# DLP.net
KiCad netlist of a schematic drawn in Altium Designer
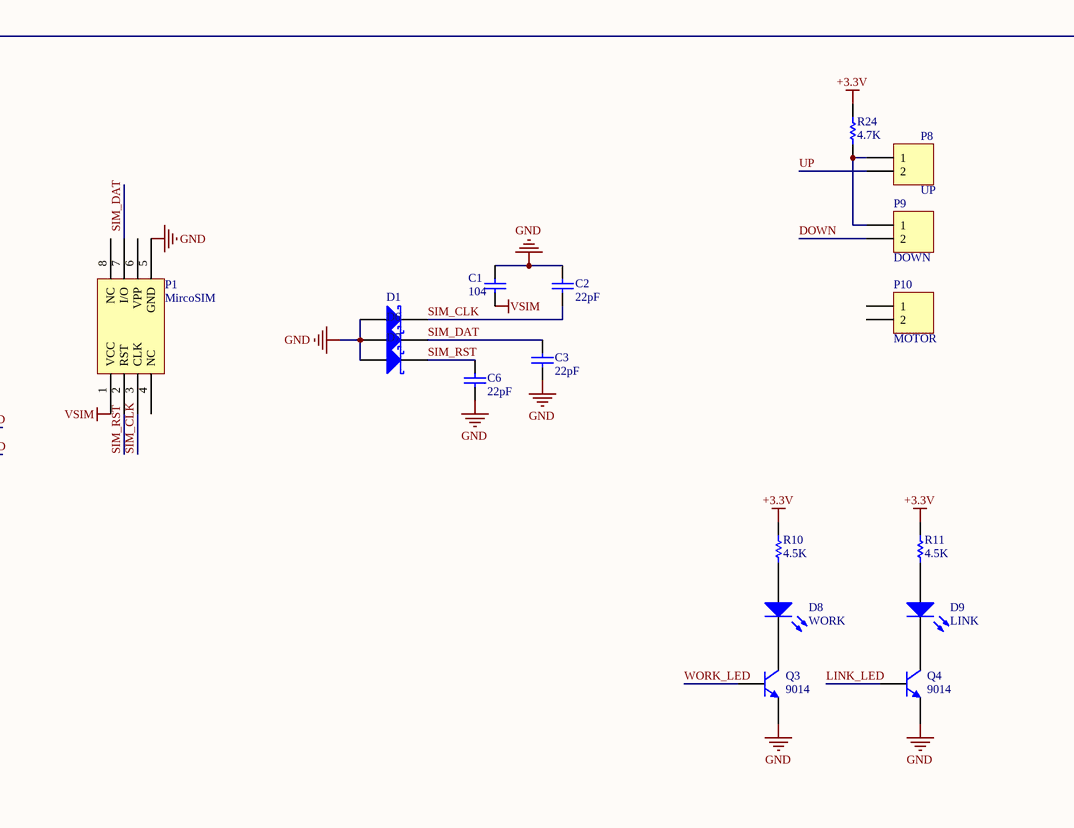
[diagram p0: DLP.SchDoc, top right]
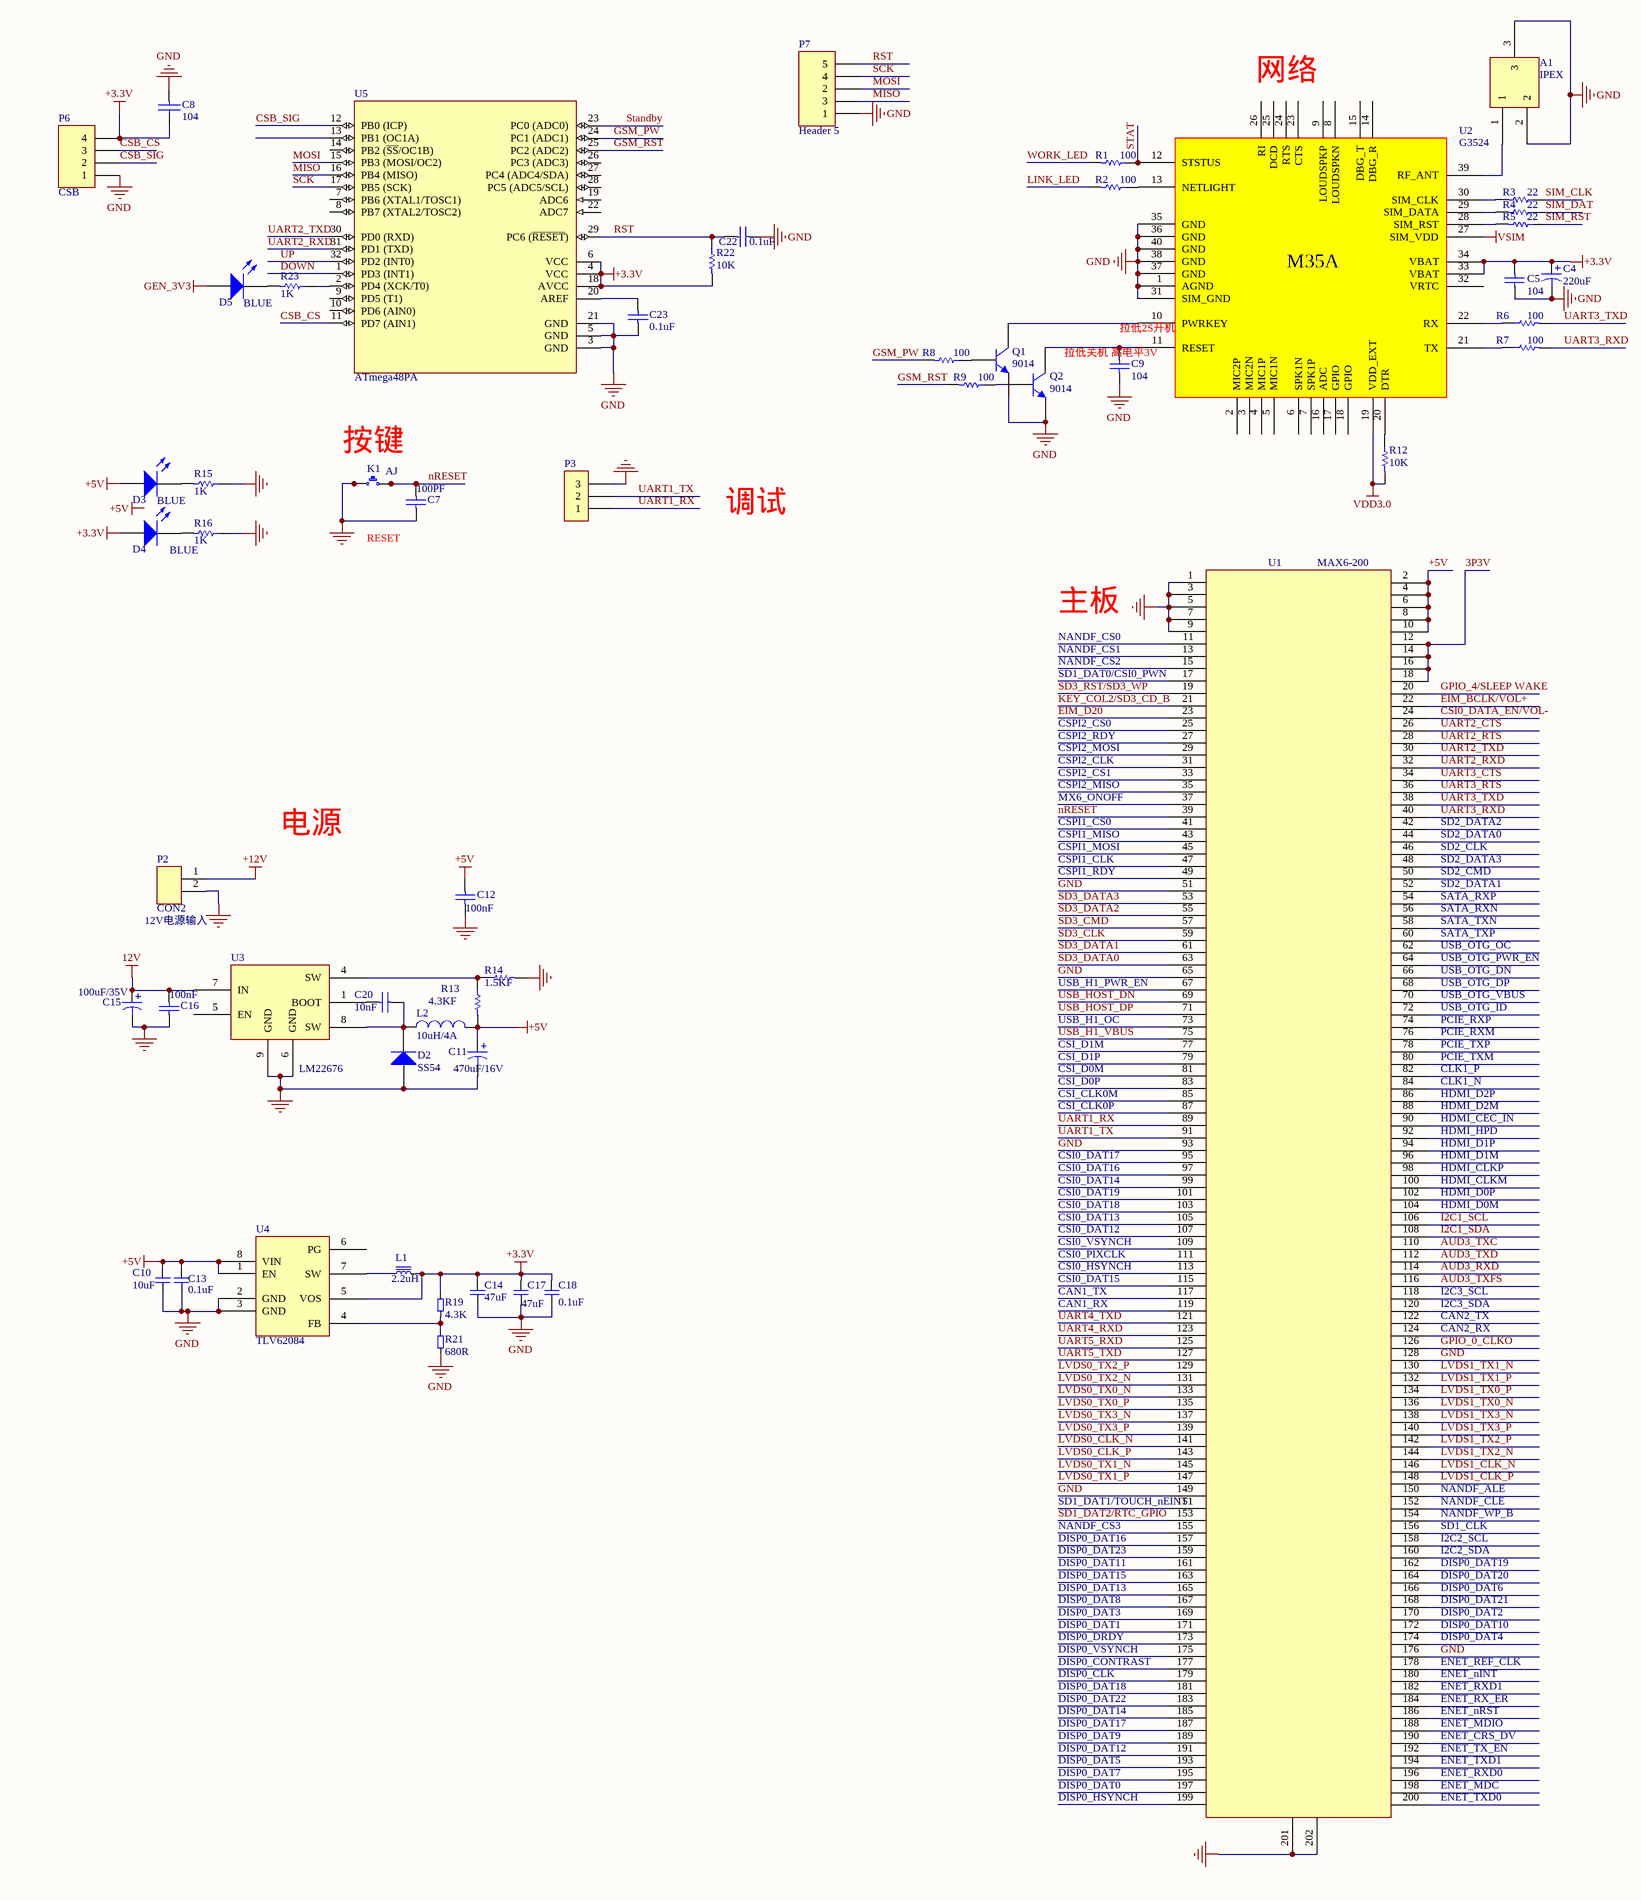
[diagram p1: DLP.SchDoc, bottom left]
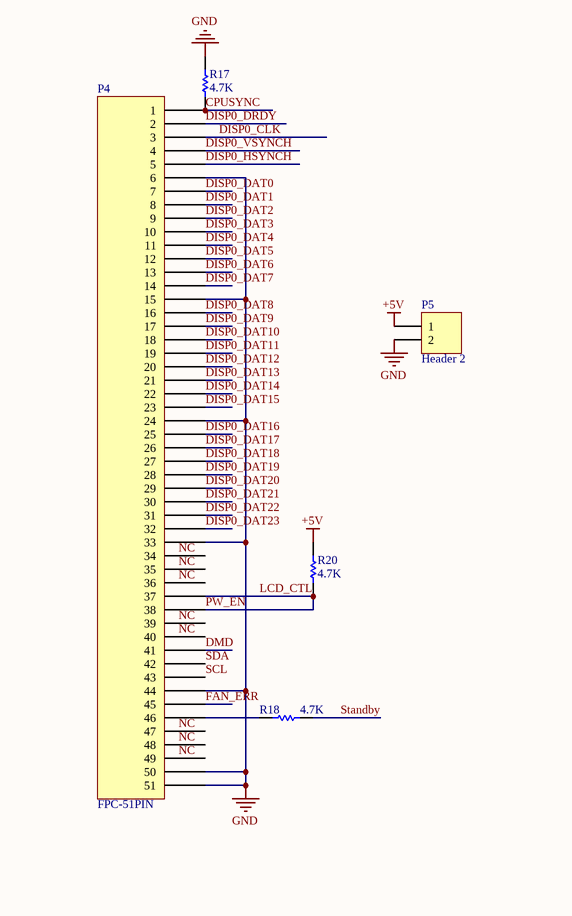
[diagram p2: DLP.SchDoc, bottom right]

(export (version "E")
  (design (tool "Eeschema 10.0.6"))
  (components
    (comp (ref "A1") (value "IPEX") (footprint "IPEX") (libsource (lib "TANK") (part "IPEX")))
    (comp (ref "C1")
      (value "104")
      (footprint "0603")
      (description "Capacitor")
      (fields (field (name "Comment") "Cap") (field (name "PUBLISHER") "Altium Limited"))
      (libsource (lib "Miscellaneous Devices") (part "Cap"))
    )
    (comp (ref "C2")
      (value "22pF")
      (footprint "0603")
      (description "Capacitor")
      (fields (field (name "Comment") "Cap") (field (name "PUBLISHER") "Altium Limited"))
      (libsource (lib "Miscellaneous Devices") (part "Cap"))
    )
    (comp (ref "C3")
      (value "22pF")
      (footprint "0603")
      (description "Capacitor")
      (fields (field (name "Comment") "Cap") (field (name "PUBLISHER") "Altium Limited"))
      (libsource (lib "Miscellaneous Devices") (part "Cap"))
    )
    (comp (ref "C4")
      (value "220uF")
      (footprint "C7343")
      (description "Polarized Capacitor (Surface Mount)")
      (fields (field (name "Comment") "Cap Pol3") (field (name "PUBLISHER") "Altium Limited"))
      (libsource (lib "Miscellaneous Devices") (part "Cap Pol3"))
    )
    (comp (ref "C5")
      (value "104")
      (footprint "0603")
      (description "Capacitor")
      (fields (field (name "Comment") "Cap") (field (name "PUBLISHER") "Altium Limited"))
      (libsource (lib "Miscellaneous Devices") (part "Cap"))
    )
    (comp (ref "C6")
      (value "22pF")
      (footprint "0603")
      (description "Capacitor")
      (fields (field (name "Comment") "Cap") (field (name "PUBLISHER") "Altium Limited"))
      (libsource (lib "Miscellaneous Devices") (part "Cap"))
    )
    (comp (ref "C7")
      (value "100PF")
      (footprint "0603")
      (description "Capacitor")
      (libsource (lib "*") (part "Cap"))
    )
    (comp (ref "C8") (value "104") (footprint "0603") (libsource (lib "*") (part "CAP")))
    (comp (ref "C9")
      (value "104")
      (footprint "0603")
      (description "Capacitor")
      (fields (field (name "Comment") "Cap") (field (name "PUBLISHER") "Altium Limited"))
      (libsource (lib "Miscellaneous Devices") (part "Cap"))
    )
    (comp (ref "C10")
      (value "10uF")
      (footprint "0603")
      (description "电容")
      (libsource (lib "LDT-SCH") (part "电容"))
    )
    (comp (ref "C11")
      (value "470uF/16V")
      (footprint "C7343")
      (description "Polarized Capacitor (Radial)")
      (libsource (lib "*") (part "Cap Pol1"))
    )
    (comp (ref "C12")
      (value "100nF")
      (footprint "0603")
      (description "Capacitor")
      (libsource (lib "*") (part "Cap"))
    )
    (comp (ref "C13")
      (value "0.1uF")
      (footprint "0603")
      (description "电容")
      (libsource (lib "LDT-SCH") (part "电容"))
    )
    (comp (ref "C14")
      (value "47uF")
      (footprint "C1206")
      (description "电容")
      (libsource (lib "LDT-SCH") (part "电容"))
    )
    (comp (ref "C15")
      (value "100uF/35V")
      (footprint "C7343")
      (description "Polarized Capacitor (Radial)")
      (libsource (lib "*") (part "Cap Pol1"))
    )
    (comp (ref "C16")
      (value "100nF")
      (footprint "0603")
      (description "Capacitor")
      (libsource (lib "*") (part "Cap"))
    )
    (comp (ref "C17")
      (value "47uF")
      (footprint "C1206")
      (description "电容")
      (libsource (lib "LDT-SCH") (part "电容"))
    )
    (comp (ref "C18")
      (value "0.1uF")
      (footprint "0603")
      (description "电容")
      (libsource (lib "LDT-SCH") (part "电容"))
    )
    (comp (ref "C20")
      (value "10nF")
      (footprint "0603")
      (description "Capacitor")
      (libsource (lib "*") (part "Cap"))
    )
    (comp (ref "C22")
      (value "0.1uF")
      (footprint "0603")
      (description "Capacitor")
      (fields (field (name "Comment") "Cap") (field (name "PUBLISHER") "Altium Limited"))
      (libsource (lib "Miscellaneous Devices") (part "Cap"))
    )
    (comp (ref "C23")
      (value "0.1uF")
      (footprint "0603")
      (description "Capacitor")
      (fields (field (name "Comment") "Cap") (field (name "PUBLISHER") "Altium Limited"))
      (libsource (lib "Miscellaneous Devices") (part "Cap"))
    )
    (comp (ref "D1")
      (value "RL0603E012M100K")
      (footprint "0603")
      (description "Schottky Rectifier")
      (fields (field (name "PUBLISHER") "Altium Limited"))
      (libsource (lib "Miscellaneous Devices") (part "Diode 18TQ045"))
    )
    (comp (ref "D2")
      (value "SS54")
      (footprint "SMA")
      (description "3 Amp Medium Power Silicon Rectifier Diode")
      (libsource (lib "*") (part "Diode 1N5408"))
    )
    (comp (ref "D3")
      (value "BLUE")
      (footprint "0603-LED")
      (description "Typical RED, GREEN, YELLOW, AMBER GaAs LED")
      (libsource (lib "*") (part "LED2"))
    )
    (comp (ref "D4")
      (value "BLUE")
      (footprint "0603-LED")
      (description "Typical RED, GREEN, YELLOW, AMBER GaAs LED")
      (libsource (lib "*") (part "LED2"))
    )
    (comp (ref "D5")
      (value "BLUE")
      (footprint "0603-LED")
      (description "Typical RED, GREEN, YELLOW, AMBER GaAs LED")
      (libsource (lib "*") (part "LED2"))
    )
    (comp (ref "D6")
      (value "RL0603E012M100K")
      (footprint "0603")
      (description "Schottky Rectifier")
      (fields (field (name "PUBLISHER") "Altium Limited"))
      (libsource (lib "Miscellaneous Devices") (part "Diode 18TQ045"))
    )
    (comp (ref "D7")
      (value "RL0603E012M100K")
      (footprint "0603")
      (description "Schottky Rectifier")
      (fields (field (name "PUBLISHER") "Altium Limited"))
      (libsource (lib "Miscellaneous Devices") (part "Diode 18TQ045"))
    )
    (comp (ref "D8")
      (value "WORK")
      (footprint "0603-LED")
      (description "Typical RED, GREEN, YELLOW, AMBER GaAs LED")
      (fields (field (name "PUBLISHER") "Altium Limited"))
      (libsource (lib "Miscellaneous Devices") (part "LED2"))
    )
    (comp (ref "D9")
      (value "LINK")
      (footprint "0603-LED")
      (description "Typical RED, GREEN, YELLOW, AMBER GaAs LED")
      (fields (field (name "PUBLISHER") "Altium Limited"))
      (libsource (lib "Miscellaneous Devices") (part "LED2"))
    )
    (comp (ref "K1") (value "AJ") (footprint "4*4*1.5") (libsource (lib "*") (part "KEY_1")))
    (comp (ref "L1") (value "2.2uH") (footprint "L-6045") (libsource (lib "LDT-SCH") (part "功率电感")))
    (comp (ref "L2")
      (value "10uH/4A")
      (footprint "L-8040")
      (description "Inductor")
      (libsource (lib "*") (part "Inductor"))
    )
    (comp (ref "P1") (value "MircoSIM") (footprint "Micro SIM") (libsource (lib "TANK") (part "MircoSIM")))
    (comp (ref "P2") (value "CON2") (footprint "PH2.0-2P") (libsource (lib "*") (part "CON2")))
    (comp (ref "P3")
      (value "~")
      (footprint "HDR1X3")
      (description "Connector")
      (libsource (lib "*") (part "CON3"))
    )
    (comp (ref "P4")
      (value "FPC-51PIN")
      (footprint "FH26-51S-0.3SHW")
      (libsource (lib "TANK") (part "FPC-51PIN"))
    )
    (comp (ref "P5")
      (value "Header 2")
      (footprint "PH2.0-2P")
      (description "Header, 2-Pin")
      (fields (field (name "PUBLISHER") "Altium Limited"))
      (libsource (lib "Miscellaneous Connectors") (part "Header 2"))
    )
    (comp (ref "P6")
      (value "CSB")
      (footprint "HDR1X4")
      (description "Header, 4-Pin")
      (fields (field (name "PUBLISHER") "Altium Limited"))
      (libsource (lib "Miscellaneous Connectors") (part "Header 4"))
    )
    (comp (ref "P7")
      (value "Header 5")
      (footprint "HDR1X5")
      (description "Header, 5-Pin")
      (fields (field (name "PUBLISHER") "Altium Limited"))
      (libsource (lib "Miscellaneous Connectors") (part "Header 5"))
    )
    (comp (ref "P8")
      (value "UP")
      (footprint "1.25-2P")
      (description "Header, 2-Pin")
      (fields (field (name "PUBLISHER") "Altium Limited"))
      (libsource (lib "Miscellaneous Connectors") (part "Header 2"))
    )
    (comp (ref "P9")
      (value "DOWN")
      (footprint "1.25-2P")
      (description "Header, 2-Pin")
      (fields (field (name "PUBLISHER") "Altium Limited"))
      (libsource (lib "Miscellaneous Connectors") (part "Header 2"))
    )
    (comp (ref "P10")
      (value "MOTOR")
      (footprint "1.25-2P")
      (description "Header, 2-Pin")
      (fields (field (name "PUBLISHER") "Altium Limited"))
      (libsource (lib "Miscellaneous Connectors") (part "Header 2"))
    )
    (comp (ref "Q1")
      (value "9014")
      (footprint "SOT-23-NPN")
      (description "NPN General Purpose Amplifier")
      (fields (field (name "Comment") "NPN") (field (name "PUBLISHER") "Altium Limited"))
      (libsource (lib "FSC Discrete BJT") (part "2N5551"))
    )
    (comp (ref "Q2")
      (value "9014")
      (footprint "SOT-23-NPN")
      (description "NPN General Purpose Amplifier")
      (fields (field (name "Comment") "NPN") (field (name "PUBLISHER") "Altium Limited"))
      (libsource (lib "FSC Discrete BJT") (part "2N5551"))
    )
    (comp (ref "Q3")
      (value "9014")
      (footprint "SOT-23-NPN")
      (description "NPN General Purpose Amplifier")
      (fields (field (name "Comment") "NPN") (field (name "PUBLISHER") "Altium Limited"))
      (libsource (lib "FSC Discrete BJT") (part "2N5551"))
    )
    (comp (ref "Q4")
      (value "9014")
      (footprint "SOT-23-NPN")
      (description "NPN General Purpose Amplifier")
      (fields (field (name "Comment") "NPN") (field (name "PUBLISHER") "Altium Limited"))
      (libsource (lib "FSC Discrete BJT") (part "2N5551"))
    )
    (comp (ref "R1")
      (value "100")
      (footprint "0603")
      (description "Resistor")
      (fields (field (name "Comment") "Res1") (field (name "PUBLISHER") "Altium Limited"))
      (libsource (lib "Miscellaneous Devices") (part "Res1"))
    )
    (comp (ref "R2")
      (value "100")
      (footprint "0603")
      (description "Resistor")
      (fields (field (name "Comment") "Res1") (field (name "PUBLISHER") "Altium Limited"))
      (libsource (lib "Miscellaneous Devices") (part "Res1"))
    )
    (comp (ref "R3")
      (value "22")
      (footprint "0603")
      (description "Resistor")
      (fields (field (name "Comment") "Res1") (field (name "PUBLISHER") "Altium Limited"))
      (libsource (lib "Miscellaneous Devices") (part "Res1"))
    )
    (comp (ref "R4")
      (value "22")
      (footprint "0603")
      (description "Resistor")
      (fields (field (name "Comment") "Res1") (field (name "PUBLISHER") "Altium Limited"))
      (libsource (lib "Miscellaneous Devices") (part "Res1"))
    )
    (comp (ref "R5")
      (value "22")
      (footprint "0603")
      (description "Resistor")
      (fields (field (name "Comment") "Res1") (field (name "PUBLISHER") "Altium Limited"))
      (libsource (lib "Miscellaneous Devices") (part "Res1"))
    )
    (comp (ref "R6")
      (value "100")
      (footprint "0603")
      (description "Resistor")
      (fields (field (name "Comment") "Res1") (field (name "PUBLISHER") "Altium Limited"))
      (libsource (lib "Miscellaneous Devices") (part "Res1"))
    )
    (comp (ref "R7")
      (value "100")
      (footprint "0603")
      (description "Resistor")
      (fields (field (name "Comment") "Res1") (field (name "PUBLISHER") "Altium Limited"))
      (libsource (lib "Miscellaneous Devices") (part "Res1"))
    )
    (comp (ref "R8")
      (value "100")
      (footprint "0603")
      (description "Resistor")
      (fields (field (name "Comment") "Res1") (field (name "PUBLISHER") "Altium Limited"))
      (libsource (lib "Miscellaneous Devices") (part "Res1"))
    )
    (comp (ref "R9")
      (value "100")
      (footprint "0603")
      (description "Resistor")
      (fields (field (name "Comment") "Res1") (field (name "PUBLISHER") "Altium Limited"))
      (libsource (lib "Miscellaneous Devices") (part "Res1"))
    )
    (comp (ref "R10")
      (value "4.5K")
      (footprint "0603")
      (description "Resistor")
      (fields (field (name "Comment") "Res1") (field (name "PUBLISHER") "Altium Limited"))
      (libsource (lib "Miscellaneous Devices") (part "Res1"))
    )
    (comp (ref "R11")
      (value "4.5K")
      (footprint "0603")
      (description "Resistor")
      (fields (field (name "Comment") "Res1") (field (name "PUBLISHER") "Altium Limited"))
      (libsource (lib "Miscellaneous Devices") (part "Res1"))
    )
    (comp (ref "R12")
      (value "10K")
      (footprint "0603")
      (description "Resistor")
      (fields (field (name "Comment") "Res1") (field (name "PUBLISHER") "Altium Limited"))
      (libsource (lib "Miscellaneous Devices") (part "Res1"))
    )
    (comp (ref "R13")
      (value "4.3KF")
      (footprint "0603")
      (description "Resistor")
      (libsource (lib "*") (part "Res1"))
    )
    (comp (ref "R14")
      (value "1.5KF")
      (footprint "0603")
      (description "Resistor")
      (libsource (lib "*") (part "Res1"))
    )
    (comp (ref "R15")
      (value "1K")
      (footprint "0603")
      (description "Resistor")
      (libsource (lib "*") (part "Res1"))
    )
    (comp (ref "R16")
      (value "1K")
      (footprint "0603")
      (description "Resistor")
      (libsource (lib "*") (part "Res1"))
    )
    (comp (ref "R17")
      (value "4.7K")
      (footprint "0603")
      (description "Resistor")
      (fields (field (name "Comment") "Res1") (field (name "PUBLISHER") "Altium Limited"))
      (libsource (lib "Miscellaneous Devices") (part "Res1"))
    )
    (comp (ref "R18")
      (value "4.7K")
      (footprint "0603")
      (description "Resistor")
      (fields (field (name "Comment") "Res1") (field (name "PUBLISHER") "Altium Limited"))
      (libsource (lib "Miscellaneous Devices") (part "Res1"))
    )
    (comp (ref "R19")
      (value "4.3K")
      (footprint "0603")
      (description "电阻")
      (libsource (lib "LDT-SCH") (part "电阻"))
    )
    (comp (ref "R20")
      (value "4.7K")
      (footprint "0603")
      (description "Resistor")
      (fields (field (name "Comment") "Res1") (field (name "PUBLISHER") "Altium Limited"))
      (libsource (lib "Miscellaneous Devices") (part "Res1"))
    )
    (comp (ref "R21")
      (value "680R")
      (footprint "0603")
      (description "电阻")
      (libsource (lib "LDT-SCH") (part "电阻"))
    )
    (comp (ref "R22")
      (value "10K")
      (footprint "0603")
      (description "Resistor")
      (fields (field (name "Comment") "Res1") (field (name "PUBLISHER") "Altium Limited"))
      (libsource (lib "Miscellaneous Devices") (part "Res1"))
    )
    (comp (ref "R23")
      (value "1K")
      (footprint "0603")
      (description "Resistor")
      (libsource (lib "*") (part "Res1"))
    )
    (comp (ref "R24")
      (value "4.7K")
      (footprint "0603")
      (description "Resistor")
      (fields (field (name "Comment") "Res1") (field (name "PUBLISHER") "Altium Limited"))
      (libsource (lib "Miscellaneous Devices") (part "Res1"))
    )
    (comp (ref "U1") (value "MAX6-200") (footprint "SO-DIMM 200") (libsource (lib "*") (part "MAX6-200")))
    (comp (ref "U2") (value "G3524") (footprint "G3524") (libsource (lib "TANK") (part "G3524")))
    (comp (ref "U3") (value "LM22676") (footprint "SO-8HP") (libsource (lib "*") (part "LM22676")))
    (comp (ref "U4") (value "TLV62084") (footprint "WSON8") (libsource (lib "Tank") (part "TLV62084")))
    (comp (ref "U5")
      (value "ATmega48PA")
      (footprint "32A_M")
      (description "8-Bit AVR Microcontroller with 8K Bytes of In-System Programmable Flash Memory")
      (fields (field (name "PUBLISHER") "Altium Limited"))
      (libsource (lib "Atmel Microcontroller 8-Bit AVR") (part "ATmega8-16AC"))
    )
  )
  (nets
    (net (code "1") (name "+3.3V") (class "Default")
      (node (ref "C14") (pin "1") (pintype "passive"))
      (node (ref "C17") (pin "1") (pintype "passive"))
      (node (ref "C18") (pin "1") (pintype "passive"))
      (node (ref "C4") (pin "1") (pinfunction "1_1") (pintype "passive"))
      (node (ref "C5") (pin "2") (pinfunction "2_2") (pintype "passive"))
      (node (ref "C8") (pin "2") (pintype "passive"))
      (node (ref "D4") (pin "1") (pinfunction "A_1") (pintype "passive"))
      (node (ref "L1") (pin "2") (pintype "passive"))
      (node (ref "P6") (pin "4") (pinfunction "4_4") (pintype "passive"))
      (node (ref "R10") (pin "1") (pinfunction "1_1") (pintype "passive"))
      (node (ref "R11") (pin "1") (pinfunction "1_1") (pintype "passive"))
      (node (ref "R19") (pin "2") (pintype "passive"))
      (node (ref "R22") (pin "2") (pinfunction "2_2") (pintype "passive"))
      (node (ref "R24") (pin "1") (pinfunction "1_1") (pintype "passive"))
      (node (ref "U2") (pin "33") (pinfunction "VBAT_33") (pintype "passive"))
      (node (ref "U2") (pin "34") (pinfunction "VBAT_34") (pintype "passive"))
      (node (ref "U4") (pin "5") (pinfunction "VOS_5") (pintype "passive"))
      (node (ref "U5") (pin "18") (pinfunction "AVCC_18") (pintype "power_in"))
      (node (ref "U5") (pin "4") (pinfunction "VCC_4") (pintype "power_in"))
      (node (ref "U5") (pin "6") (pinfunction "VCC_6") (pintype "power_in"))
    )
    (net (code "2") (name "+5V") (class "Default")
      (node (ref "C10") (pin "1") (pintype "passive"))
      (node (ref "C11") (pin "1") (pinfunction "1_1") (pintype "passive"))
      (node (ref "C12") (pin "2") (pinfunction "2_2") (pintype "passive"))
      (node (ref "C13") (pin "1") (pintype "passive"))
      (node (ref "D3") (pin "1") (pinfunction "A_1") (pintype "passive"))
      (node (ref "L2") (pin "2") (pinfunction "2_2") (pintype "passive"))
      (node (ref "P5") (pin "1") (pinfunction "1_1") (pintype "passive"))
      (node (ref "R13") (pin "2") (pinfunction "2_2") (pintype "passive"))
      (node (ref "R20") (pin "1") (pinfunction "1_1") (pintype "passive"))
      (node (ref "U1") (pin "10") (pintype "passive"))
      (node (ref "U1") (pin "2") (pintype "passive"))
      (node (ref "U1") (pin "4") (pintype "passive"))
      (node (ref "U1") (pin "6") (pintype "passive"))
      (node (ref "U1") (pin "8") (pintype "passive"))
      (node (ref "U4") (pin "1") (pinfunction "EN_1") (pintype "passive"))
      (node (ref "U4") (pin "8") (pinfunction "VIN_8") (pintype "passive"))
    )
    (net (code "3") (name "+12V") (class "Default")
      (node (ref "P2") (pin "1") (pinfunction "1_1") (pintype "passive"))
    )
    (net (code "4") (name "/3P3V") (class "Default")
      (node (ref "U1") (pin "12") (pintype "passive"))
      (node (ref "U1") (pin "14") (pintype "passive"))
      (node (ref "U1") (pin "16") (pintype "passive"))
      (node (ref "U1") (pin "18") (pintype "passive"))
    )
    (net (code "5") (name "/AUD3_RXD") (class "Default") (node (ref "U1") (pin "114") (pintype "passive")))
    (net (code "6") (name "/AUD3_TXC") (class "Default") (node (ref "U1") (pin "110") (pintype "passive")))
    (net (code "7") (name "/AUD3_TXD") (class "Default") (node (ref "U1") (pin "112") (pintype "passive")))
    (net (code "8") (name "/AUD3_TXFS") (class "Default") (node (ref "U1") (pin "116") (pintype "passive")))
    (net (code "9") (name "/CAN1_RX") (class "Default") (node (ref "U1") (pin "119") (pintype "passive")))
    (net (code "10") (name "/CAN1_TX") (class "Default") (node (ref "U1") (pin "117") (pintype "passive")))
    (net (code "11") (name "/CAN2_RX") (class "Default") (node (ref "U1") (pin "124") (pintype "passive")))
    (net (code "12") (name "/CAN2_TX") (class "Default") (node (ref "U1") (pin "122") (pintype "passive")))
    (net (code "13") (name "/CLK1_N") (class "Default") (node (ref "U1") (pin "84") (pintype "passive")))
    (net (code "14") (name "/CLK1_P") (class "Default") (node (ref "U1") (pin "82") (pintype "passive")))
    (net (code "15") (name "/CPUSYNC") (class "Default")
      (node (ref "P4") (pin "1") (pinfunction "1_1") (pintype "passive"))
      (node (ref "R17") (pin "2") (pinfunction "2_2") (pintype "passive"))
    )
    (net (code "16") (name "/CSB_CS") (class "Default")
      (node (ref "P6") (pin "3") (pinfunction "3_3") (pintype "passive"))
      (node (ref "U5") (pin "11") (pinfunction "PD7_(AIN1)_11") (pintype "bidirectional"))
    )
    (net (code "17") (name "/CSB_SIG") (class "Default")
      (node (ref "P6") (pin "2") (pinfunction "2_2") (pintype "passive"))
      (node (ref "U5") (pin "12") (pinfunction "PB0_(ICP)_12") (pintype "bidirectional"))
    )
    (net (code "18") (name "/CSI0_DAT12") (class "Default") (node (ref "U1") (pin "107") (pintype "passive")))
    (net (code "19") (name "/CSI0_DAT13") (class "Default") (node (ref "U1") (pin "105") (pintype "passive")))
    (net (code "20") (name "/CSI0_DAT14") (class "Default") (node (ref "U1") (pin "99") (pintype "passive")))
    (net (code "21") (name "/CSI0_DAT15") (class "Default") (node (ref "U1") (pin "115") (pintype "passive")))
    (net (code "22") (name "/CSI0_DAT16") (class "Default") (node (ref "U1") (pin "97") (pintype "passive")))
    (net (code "23") (name "/CSI0_DAT17") (class "Default") (node (ref "U1") (pin "95") (pintype "passive")))
    (net (code "24") (name "/CSI0_DAT18") (class "Default") (node (ref "U1") (pin "103") (pintype "passive")))
    (net (code "25") (name "/CSI0_DAT19") (class "Default") (node (ref "U1") (pin "101") (pintype "passive")))
    (net (code "26") (name "/CSI0_DATA_EN{slash}VOL-") (class "Default")
      (node (ref "U1") (pin "24") (pintype "passive"))
    )
    (net (code "27") (name "/CSI0_HSYNCH") (class "Default")
      (node (ref "U1") (pin "113") (pintype "passive"))
    )
    (net (code "28") (name "/CSI0_PIXCLK") (class "Default")
      (node (ref "U1") (pin "111") (pintype "passive"))
    )
    (net (code "29") (name "/CSI0_VSYNCH") (class "Default")
      (node (ref "U1") (pin "109") (pintype "passive"))
    )
    (net (code "30") (name "/CSI_CLK0M") (class "Default") (node (ref "U1") (pin "85") (pintype "passive")))
    (net (code "31") (name "/CSI_CLK0P") (class "Default") (node (ref "U1") (pin "87") (pintype "passive")))
    (net (code "32") (name "/CSI_D0M") (class "Default") (node (ref "U1") (pin "81") (pintype "passive")))
    (net (code "33") (name "/CSI_D0P") (class "Default") (node (ref "U1") (pin "83") (pintype "passive")))
    (net (code "34") (name "/CSI_D1M") (class "Default") (node (ref "U1") (pin "77") (pintype "passive")))
    (net (code "35") (name "/CSI_D1P") (class "Default") (node (ref "U1") (pin "79") (pintype "passive")))
    (net (code "36") (name "/CSPI1_CLK") (class "Default") (node (ref "U1") (pin "47") (pintype "passive")))
    (net (code "37") (name "/CSPI1_CS0") (class "Default") (node (ref "U1") (pin "41") (pintype "passive")))
    (net (code "38") (name "/CSPI1_MISO") (class "Default") (node (ref "U1") (pin "43") (pintype "passive")))
    (net (code "39") (name "/CSPI1_MOSI") (class "Default") (node (ref "U1") (pin "45") (pintype "passive")))
    (net (code "40") (name "/CSPI1_RDY") (class "Default") (node (ref "U1") (pin "49") (pintype "passive")))
    (net (code "41") (name "/CSPI2_CLK") (class "Default") (node (ref "U1") (pin "31") (pintype "passive")))
    (net (code "42") (name "/CSPI2_CS0") (class "Default") (node (ref "U1") (pin "25") (pintype "passive")))
    (net (code "43") (name "/CSPI2_CS1") (class "Default") (node (ref "U1") (pin "33") (pintype "passive")))
    (net (code "44") (name "/CSPI2_MISO") (class "Default") (node (ref "U1") (pin "35") (pintype "passive")))
    (net (code "45") (name "/CSPI2_MOSI") (class "Default") (node (ref "U1") (pin "29") (pintype "passive")))
    (net (code "46") (name "/CSPI2_RDY") (class "Default") (node (ref "U1") (pin "27") (pintype "passive")))
    (net (code "47") (name "/DISP0_CLK") (class "Default")
      (node (ref "P4") (pin "3") (pinfunction "3_3") (pintype "passive"))
      (node (ref "U1") (pin "179") (pintype "passive"))
    )
    (net (code "48") (name "/DISP0_CONTRAST") (class "Default")
      (node (ref "U1") (pin "177") (pintype "passive"))
    )
    (net (code "49") (name "/DISP0_DAT0") (class "Default")
      (node (ref "P4") (pin "7") (pinfunction "7_7") (pintype "passive"))
      (node (ref "U1") (pin "197") (pintype "passive"))
    )
    (net (code "50") (name "/DISP0_DAT1") (class "Default")
      (node (ref "P4") (pin "8") (pinfunction "8_8") (pintype "passive"))
      (node (ref "U1") (pin "171") (pintype "passive"))
    )
    (net (code "51") (name "/DISP0_DAT2") (class "Default")
      (node (ref "P4") (pin "9") (pinfunction "9_9") (pintype "passive"))
      (node (ref "U1") (pin "170") (pintype "passive"))
    )
    (net (code "52") (name "/DISP0_DAT3") (class "Default")
      (node (ref "P4") (pin "10") (pinfunction "10_10") (pintype "passive"))
      (node (ref "U1") (pin "169") (pintype "passive"))
    )
    (net (code "53") (name "/DISP0_DAT4") (class "Default")
      (node (ref "P4") (pin "11") (pinfunction "11_11") (pintype "passive"))
      (node (ref "U1") (pin "174") (pintype "passive"))
    )
    (net (code "54") (name "/DISP0_DAT5") (class "Default")
      (node (ref "P4") (pin "12") (pinfunction "12_12") (pintype "passive"))
      (node (ref "U1") (pin "193") (pintype "passive"))
    )
    (net (code "55") (name "/DISP0_DAT6") (class "Default")
      (node (ref "P4") (pin "13") (pinfunction "13_13") (pintype "passive"))
      (node (ref "U1") (pin "166") (pintype "passive"))
    )
    (net (code "56") (name "/DISP0_DAT7") (class "Default")
      (node (ref "P4") (pin "14") (pinfunction "14_14") (pintype "passive"))
      (node (ref "U1") (pin "195") (pintype "passive"))
    )
    (net (code "57") (name "/DISP0_DAT8") (class "Default")
      (node (ref "P4") (pin "16") (pinfunction "16_16") (pintype "passive"))
      (node (ref "U1") (pin "167") (pintype "passive"))
    )
    (net (code "58") (name "/DISP0_DAT9") (class "Default")
      (node (ref "P4") (pin "17") (pinfunction "17_17") (pintype "passive"))
      (node (ref "U1") (pin "189") (pintype "passive"))
    )
    (net (code "59") (name "/DISP0_DAT10") (class "Default")
      (node (ref "P4") (pin "18") (pinfunction "18_18") (pintype "passive"))
      (node (ref "U1") (pin "172") (pintype "passive"))
    )
    (net (code "60") (name "/DISP0_DAT11") (class "Default")
      (node (ref "P4") (pin "19") (pinfunction "19_19") (pintype "passive"))
      (node (ref "U1") (pin "161") (pintype "passive"))
    )
    (net (code "61") (name "/DISP0_DAT12") (class "Default")
      (node (ref "P4") (pin "20") (pinfunction "20_20") (pintype "passive"))
      (node (ref "U1") (pin "191") (pintype "passive"))
    )
    (net (code "62") (name "/DISP0_DAT13") (class "Default")
      (node (ref "P4") (pin "21") (pinfunction "21_21") (pintype "passive"))
      (node (ref "U1") (pin "165") (pintype "passive"))
    )
    (net (code "63") (name "/DISP0_DAT14") (class "Default")
      (node (ref "P4") (pin "22") (pinfunction "22_22") (pintype "passive"))
      (node (ref "U1") (pin "185") (pintype "passive"))
    )
    (net (code "64") (name "/DISP0_DAT15") (class "Default")
      (node (ref "P4") (pin "23") (pinfunction "23_23") (pintype "passive"))
      (node (ref "U1") (pin "163") (pintype "passive"))
    )
    (net (code "65") (name "/DISP0_DAT16") (class "Default")
      (node (ref "P4") (pin "25") (pinfunction "25_25") (pintype "passive"))
      (node (ref "U1") (pin "157") (pintype "passive"))
    )
    (net (code "66") (name "/DISP0_DAT17") (class "Default")
      (node (ref "P4") (pin "26") (pinfunction "26_26") (pintype "passive"))
      (node (ref "U1") (pin "187") (pintype "passive"))
    )
    (net (code "67") (name "/DISP0_DAT18") (class "Default")
      (node (ref "P4") (pin "27") (pinfunction "27_27") (pintype "passive"))
      (node (ref "U1") (pin "181") (pintype "passive"))
    )
    (net (code "68") (name "/DISP0_DAT19") (class "Default")
      (node (ref "P4") (pin "28") (pinfunction "28_28") (pintype "passive"))
      (node (ref "U1") (pin "162") (pintype "passive"))
    )
    (net (code "69") (name "/DISP0_DAT20") (class "Default")
      (node (ref "P4") (pin "29") (pinfunction "29_29") (pintype "passive"))
      (node (ref "U1") (pin "164") (pintype "passive"))
    )
    (net (code "70") (name "/DISP0_DAT21") (class "Default")
      (node (ref "P4") (pin "30") (pinfunction "30_30") (pintype "passive"))
      (node (ref "U1") (pin "168") (pintype "passive"))
    )
    (net (code "71") (name "/DISP0_DAT22") (class "Default")
      (node (ref "P4") (pin "31") (pinfunction "31_31") (pintype "passive"))
      (node (ref "U1") (pin "183") (pintype "passive"))
    )
    (net (code "72") (name "/DISP0_DAT23") (class "Default")
      (node (ref "P4") (pin "32") (pinfunction "32_32") (pintype "passive"))
      (node (ref "U1") (pin "159") (pintype "passive"))
    )
    (net (code "73") (name "/DISP0_DRDY") (class "Default")
      (node (ref "P4") (pin "2") (pinfunction "2_2") (pintype "passive"))
      (node (ref "U1") (pin "173") (pintype "passive"))
    )
    (net (code "74") (name "/DISP0_HSYNCH") (class "Default")
      (node (ref "P4") (pin "5") (pinfunction "5_5") (pintype "passive"))
      (node (ref "U1") (pin "199") (pintype "passive"))
    )
    (net (code "75") (name "/DISP0_VSYNCH") (class "Default")
      (node (ref "P4") (pin "4") (pinfunction "4_4") (pintype "passive"))
      (node (ref "U1") (pin "175") (pintype "passive"))
    )
    (net (code "76") (name "/DMD") (class "Default")
      (node (ref "P4") (pin "41") (pinfunction "41_41") (pintype "passive"))
    )
    (net (code "77") (name "/DOWN") (class "Default")
      (node (ref "P9") (pin "2") (pinfunction "2_2") (pintype "passive"))
      (node (ref "U5") (pin "1") (pinfunction "PD3_(INT1)_1") (pintype "bidirectional"))
    )
    (net (code "78") (name "/EIM_BCLK{slash}VOL+") (class "Default")
      (node (ref "U1") (pin "22") (pintype "passive"))
    )
    (net (code "79") (name "/EIM_D20") (class "Default") (node (ref "U1") (pin "23") (pintype "passive")))
    (net (code "80") (name "/ENET_CRS_DV") (class "Default")
      (node (ref "U1") (pin "190") (pintype "passive"))
    )
    (net (code "81") (name "/ENET_MDC") (class "Default") (node (ref "U1") (pin "198") (pintype "passive")))
    (net (code "82") (name "/ENET_MDIO") (class "Default") (node (ref "U1") (pin "188") (pintype "passive")))
    (net (code "83") (name "/ENET_REF_CLK") (class "Default")
      (node (ref "U1") (pin "178") (pintype "passive"))
    )
    (net (code "84") (name "/ENET_RXD0") (class "Default") (node (ref "U1") (pin "196") (pintype "passive")))
    (net (code "85") (name "/ENET_RXD1") (class "Default") (node (ref "U1") (pin "182") (pintype "passive")))
    (net (code "86") (name "/ENET_RX_ER") (class "Default") (node (ref "U1") (pin "184") (pintype "passive")))
    (net (code "87") (name "/ENET_TXD0") (class "Default") (node (ref "U1") (pin "200") (pintype "passive")))
    (net (code "88") (name "/ENET_TXD1") (class "Default") (node (ref "U1") (pin "194") (pintype "passive")))
    (net (code "89") (name "/ENET_TX_EN") (class "Default") (node (ref "U1") (pin "192") (pintype "passive")))
    (net (code "90") (name "/ENET_nINT") (class "Default") (node (ref "U1") (pin "180") (pintype "passive")))
    (net (code "91") (name "/ENET_nRST") (class "Default") (node (ref "U1") (pin "186") (pintype "passive")))
    (net (code "92") (name "/FAN_ERR") (class "Default")
      (node (ref "P4") (pin "45") (pinfunction "45_45") (pintype "passive"))
    )
    (net (code "93") (name "/GPIO_0_CLKO") (class "Default")
      (node (ref "U1") (pin "126") (pintype "passive"))
    )
    (net (code "94") (name "/GPIO_4{slash}SLEEP WAKE") (class "Default")
      (node (ref "U1") (pin "20") (pintype "passive"))
    )
    (net (code "95") (name "/GSM_PW") (class "Default")
      (node (ref "R8") (pin "2") (pinfunction "2_2") (pintype "passive"))
      (node (ref "U5") (pin "24") (pinfunction "PC1_(ADC1)_24") (pintype "bidirectional"))
    )
    (net (code "96") (name "/GSM_RST") (class "Default")
      (node (ref "R9") (pin "2") (pinfunction "2_2") (pintype "passive"))
      (node (ref "U5") (pin "25") (pinfunction "PC2_(ADC2)_25") (pintype "bidirectional"))
    )
    (net (code "97") (name "/HDMI_CEC_IN") (class "Default") (node (ref "U1") (pin "90") (pintype "passive")))
    (net (code "98") (name "/HDMI_CLKM") (class "Default") (node (ref "U1") (pin "100") (pintype "passive")))
    (net (code "99") (name "/HDMI_CLKP") (class "Default") (node (ref "U1") (pin "98") (pintype "passive")))
    (net (code "100") (name "/HDMI_D0M") (class "Default") (node (ref "U1") (pin "104") (pintype "passive")))
    (net (code "101") (name "/HDMI_D0P") (class "Default") (node (ref "U1") (pin "102") (pintype "passive")))
    (net (code "102") (name "/HDMI_D1M") (class "Default") (node (ref "U1") (pin "96") (pintype "passive")))
    (net (code "103") (name "/HDMI_D1P") (class "Default") (node (ref "U1") (pin "94") (pintype "passive")))
    (net (code "104") (name "/HDMI_D2M") (class "Default") (node (ref "U1") (pin "88") (pintype "passive")))
    (net (code "105") (name "/HDMI_D2P") (class "Default") (node (ref "U1") (pin "86") (pintype "passive")))
    (net (code "106") (name "/HDMI_HPD") (class "Default") (node (ref "U1") (pin "92") (pintype "passive")))
    (net (code "107") (name "/I2C1_SCL") (class "Default") (node (ref "U1") (pin "106") (pintype "passive")))
    (net (code "108") (name "/I2C1_SDA") (class "Default") (node (ref "U1") (pin "108") (pintype "passive")))
    (net (code "109") (name "/I2C2_SCL") (class "Default") (node (ref "U1") (pin "158") (pintype "passive")))
    (net (code "110") (name "/I2C2_SDA") (class "Default") (node (ref "U1") (pin "160") (pintype "passive")))
    (net (code "111") (name "/I2C3_SCL") (class "Default") (node (ref "U1") (pin "118") (pintype "passive")))
    (net (code "112") (name "/I2C3_SDA") (class "Default") (node (ref "U1") (pin "120") (pintype "passive")))
    (net (code "113") (name "/KEY_COL2{slash}SD3_CD_B") (class "Default")
      (node (ref "U1") (pin "21") (pintype "passive"))
    )
    (net (code "114") (name "/LCD_CTL") (class "Default")
      (node (ref "P4") (pin "37") (pinfunction "37_37") (pintype "passive"))
      (node (ref "P4") (pin "38") (pinfunction "38_38") (pintype "passive"))
      (node (ref "R20") (pin "2") (pinfunction "2_2") (pintype "passive"))
    )
    (net (code "115") (name "/LINK_LED") (class "Default")
      (node (ref "Q4") (pin "2") (pinfunction "B_2") (pintype "passive"))
      (node (ref "R2") (pin "2") (pinfunction "2_2") (pintype "passive"))
    )
    (net (code "116") (name "/LVDS0_CLK_N") (class "Default")
      (node (ref "U1") (pin "141") (pintype "passive"))
    )
    (net (code "117") (name "/LVDS0_CLK_P") (class "Default")
      (node (ref "U1") (pin "143") (pintype "passive"))
    )
    (net (code "118") (name "/LVDS0_TX0_N") (class "Default")
      (node (ref "U1") (pin "133") (pintype "passive"))
    )
    (net (code "119") (name "/LVDS0_TX0_P") (class "Default")
      (node (ref "U1") (pin "135") (pintype "passive"))
    )
    (net (code "120") (name "/LVDS0_TX1_N") (class "Default")
      (node (ref "U1") (pin "145") (pintype "passive"))
    )
    (net (code "121") (name "/LVDS0_TX1_P") (class "Default")
      (node (ref "U1") (pin "147") (pintype "passive"))
    )
    (net (code "122") (name "/LVDS0_TX2_N") (class "Default")
      (node (ref "U1") (pin "131") (pintype "passive"))
    )
    (net (code "123") (name "/LVDS0_TX2_P") (class "Default")
      (node (ref "U1") (pin "129") (pintype "passive"))
    )
    (net (code "124") (name "/LVDS0_TX3_N") (class "Default")
      (node (ref "U1") (pin "137") (pintype "passive"))
    )
    (net (code "125") (name "/LVDS0_TX3_P") (class "Default")
      (node (ref "U1") (pin "139") (pintype "passive"))
    )
    (net (code "126") (name "/LVDS1_CLK_N") (class "Default")
      (node (ref "U1") (pin "146") (pintype "passive"))
    )
    (net (code "127") (name "/LVDS1_CLK_P") (class "Default")
      (node (ref "U1") (pin "148") (pintype "passive"))
    )
    (net (code "128") (name "/LVDS1_TX0_N") (class "Default")
      (node (ref "U1") (pin "136") (pintype "passive"))
    )
    (net (code "129") (name "/LVDS1_TX0_P") (class "Default")
      (node (ref "U1") (pin "134") (pintype "passive"))
    )
    (net (code "130") (name "/LVDS1_TX1_N") (class "Default")
      (node (ref "U1") (pin "130") (pintype "passive"))
    )
    (net (code "131") (name "/LVDS1_TX1_P") (class "Default")
      (node (ref "U1") (pin "132") (pintype "passive"))
    )
    (net (code "132") (name "/LVDS1_TX2_N") (class "Default")
      (node (ref "U1") (pin "144") (pintype "passive"))
    )
    (net (code "133") (name "/LVDS1_TX2_P") (class "Default")
      (node (ref "U1") (pin "142") (pintype "passive"))
    )
    (net (code "134") (name "/LVDS1_TX3_N") (class "Default")
      (node (ref "U1") (pin "138") (pintype "passive"))
    )
    (net (code "135") (name "/LVDS1_TX3_P") (class "Default")
      (node (ref "U1") (pin "140") (pintype "passive"))
    )
    (net (code "136") (name "/MISO") (class "Default")
      (node (ref "P7") (pin "3") (pinfunction "3_3") (pintype "passive"))
      (node (ref "U5") (pin "16") (pinfunction "PB4_(MISO)_16") (pintype "bidirectional"))
    )
    (net (code "137") (name "/MOSI") (class "Default")
      (node (ref "P7") (pin "2") (pinfunction "2_2") (pintype "passive"))
      (node (ref "U5") (pin "15") (pinfunction "PB3_(MOSI/OC2)_15") (pintype "bidirectional"))
    )
    (net (code "138") (name "/MX6_ONOFF") (class "Default") (node (ref "U1") (pin "37") (pintype "passive")))
    (net (code "139") (name "/NANDF_ALE") (class "Default") (node (ref "U1") (pin "150") (pintype "passive")))
    (net (code "140") (name "/NANDF_CLE") (class "Default") (node (ref "U1") (pin "152") (pintype "passive")))
    (net (code "141") (name "/NANDF_CS0") (class "Default") (node (ref "U1") (pin "11") (pintype "passive")))
    (net (code "142") (name "/NANDF_CS1") (class "Default") (node (ref "U1") (pin "13") (pintype "passive")))
    (net (code "143") (name "/NANDF_CS2") (class "Default") (node (ref "U1") (pin "15") (pintype "passive")))
    (net (code "144") (name "/NANDF_CS3") (class "Default") (node (ref "U1") (pin "155") (pintype "passive")))
    (net (code "145") (name "/NANDF_WP_B") (class "Default")
      (node (ref "U1") (pin "154") (pintype "passive"))
    )
    (net (code "147") (name "/PCIE_RXM") (class "Default") (node (ref "U1") (pin "76") (pintype "passive")))
    (net (code "148") (name "/PCIE_RXP") (class "Default") (node (ref "U1") (pin "74") (pintype "passive")))
    (net (code "149") (name "/PCIE_TXM") (class "Default") (node (ref "U1") (pin "80") (pintype "passive")))
    (net (code "150") (name "/PCIE_TXP") (class "Default") (node (ref "U1") (pin "78") (pintype "passive")))
    (net (code "151") (name "/RST") (class "Default")
      (node (ref "C22") (pin "1") (pinfunction "1_1") (pintype "passive"))
      (node (ref "P7") (pin "5") (pinfunction "5_5") (pintype "passive"))
      (node (ref "R22") (pin "1") (pinfunction "1_1") (pintype "passive"))
      (node (ref "U5") (pin "29") (pinfunction "PC6_(~{RESET})_29") (pintype "bidirectional"))
    )
    (net (code "152") (name "/SATA_RXN") (class "Default") (node (ref "U1") (pin "56") (pintype "passive")))
    (net (code "153") (name "/SATA_RXP") (class "Default") (node (ref "U1") (pin "54") (pintype "passive")))
    (net (code "154") (name "/SATA_TXN") (class "Default") (node (ref "U1") (pin "58") (pintype "passive")))
    (net (code "155") (name "/SATA_TXP") (class "Default") (node (ref "U1") (pin "60") (pintype "passive")))
    (net (code "156") (name "/SCK") (class "Default")
      (node (ref "P7") (pin "4") (pinfunction "4_4") (pintype "passive"))
      (node (ref "U5") (pin "17") (pinfunction "PB5_(SCK)_17") (pintype "bidirectional"))
    )
    (net (code "157") (name "/SCL") (class "Default")
      (node (ref "P4") (pin "43") (pinfunction "43_43") (pintype "passive"))
    )
    (net (code "158") (name "/SD1_CLK") (class "Default") (node (ref "U1") (pin "156") (pintype "passive")))
    (net (code "159") (name "/SD1_DAT0{slash}CSI0_PWN") (class "Default")
      (node (ref "U1") (pin "17") (pintype "passive"))
    )
    (net (code "160") (name "/SD1_DAT1{slash}TOUCH_nEINT1") (class "Default")
      (node (ref "U1") (pin "151") (pintype "passive"))
    )
    (net (code "161") (name "/SD1_DAT2{slash}RTC_GPIO") (class "Default")
      (node (ref "U1") (pin "153") (pintype "passive"))
    )
    (net (code "162") (name "/SD2_CLK") (class "Default") (node (ref "U1") (pin "46") (pintype "passive")))
    (net (code "163") (name "/SD2_CMD") (class "Default") (node (ref "U1") (pin "50") (pintype "passive")))
    (net (code "164") (name "/SD2_DATA0") (class "Default") (node (ref "U1") (pin "44") (pintype "passive")))
    (net (code "165") (name "/SD2_DATA1") (class "Default") (node (ref "U1") (pin "52") (pintype "passive")))
    (net (code "166") (name "/SD2_DATA2") (class "Default") (node (ref "U1") (pin "42") (pintype "passive")))
    (net (code "167") (name "/SD2_DATA3") (class "Default") (node (ref "U1") (pin "48") (pintype "passive")))
    (net (code "168") (name "/SD3_CLK") (class "Default") (node (ref "U1") (pin "59") (pintype "passive")))
    (net (code "169") (name "/SD3_CMD") (class "Default") (node (ref "U1") (pin "57") (pintype "passive")))
    (net (code "170") (name "/SD3_DATA0") (class "Default") (node (ref "U1") (pin "63") (pintype "passive")))
    (net (code "171") (name "/SD3_DATA1") (class "Default") (node (ref "U1") (pin "61") (pintype "passive")))
    (net (code "172") (name "/SD3_DATA2") (class "Default") (node (ref "U1") (pin "55") (pintype "passive")))
    (net (code "173") (name "/SD3_DATA3") (class "Default") (node (ref "U1") (pin "53") (pintype "passive")))
    (net (code "174") (name "/SD3_RST{slash}SD3_WP") (class "Default")
      (node (ref "U1") (pin "19") (pintype "passive"))
    )
    (net (code "175") (name "/SDA") (class "Default")
      (node (ref "P4") (pin "42") (pinfunction "42_42") (pintype "passive"))
    )
    (net (code "176") (name "/SIM_CLK") (class "Default")
      (node (ref "C2") (pin "2") (pinfunction "2_2") (pintype "passive"))
      (node (ref "D1") (pin "1") (pinfunction "K_1") (pintype "passive"))
      (node (ref "P1") (pin "3") (pinfunction "CLK_3") (pintype "passive"))
      (node (ref "R3") (pin "1") (pinfunction "1_1") (pintype "passive"))
    )
    (net (code "177") (name "/SIM_DAT") (class "Default")
      (node (ref "C3") (pin "1") (pinfunction "1_1") (pintype "passive"))
      (node (ref "D6") (pin "1") (pinfunction "K_1") (pintype "passive"))
      (node (ref "P1") (pin "7") (pinfunction "I/O_7") (pintype "passive"))
      (node (ref "R4") (pin "1") (pinfunction "1_1") (pintype "passive"))
    )
    (net (code "178") (name "/SIM_RST") (class "Default")
      (node (ref "C6") (pin "1") (pinfunction "1_1") (pintype "passive"))
      (node (ref "D7") (pin "1") (pinfunction "K_1") (pintype "passive"))
      (node (ref "P1") (pin "2") (pinfunction "RST_2") (pintype "passive"))
      (node (ref "R5") (pin "1") (pinfunction "1_1") (pintype "passive"))
    )
    (net (code "179") (name "/STAT") (class "Default")
      (node (ref "R1") (pin "1") (pinfunction "1_1") (pintype "passive"))
      (node (ref "U2") (pin "12") (pinfunction "STSTUS_12") (pintype "passive"))
    )
    (net (code "180") (name "/Standby") (class "Default")
      (node (ref "R18") (pin "2") (pinfunction "2_2") (pintype "passive"))
      (node (ref "U5") (pin "23") (pinfunction "PC0_(ADC0)_23") (pintype "bidirectional"))
    )
    (net (code "181") (name "/UART1_RX") (class "Default")
      (node (ref "P3") (pin "1") (pinfunction "1_1") (pintype "passive"))
      (node (ref "U1") (pin "89") (pintype "passive"))
    )
    (net (code "182") (name "/UART1_TX") (class "Default")
      (node (ref "P3") (pin "2") (pinfunction "2_2") (pintype "passive"))
      (node (ref "U1") (pin "91") (pintype "passive"))
    )
    (net (code "183") (name "/UART2_CTS") (class "Default") (node (ref "U1") (pin "26") (pintype "passive")))
    (net (code "184") (name "/UART2_RTS") (class "Default") (node (ref "U1") (pin "28") (pintype "passive")))
    (net (code "185") (name "/UART2_RXD") (class "Default")
      (node (ref "U1") (pin "32") (pintype "passive"))
      (node (ref "U5") (pin "31") (pinfunction "PD1_(TXD)_31") (pintype "bidirectional"))
    )
    (net (code "186") (name "/UART2_TXD") (class "Default")
      (node (ref "U1") (pin "30") (pintype "passive"))
      (node (ref "U5") (pin "30") (pinfunction "PD0_(RXD)_30") (pintype "bidirectional"))
    )
    (net (code "187") (name "/UART3_CTS") (class "Default") (node (ref "U1") (pin "34") (pintype "passive")))
    (net (code "188") (name "/UART3_RTS") (class "Default") (node (ref "U1") (pin "36") (pintype "passive")))
    (net (code "189") (name "/UART3_RXD") (class "Default")
      (node (ref "R7") (pin "2") (pinfunction "2_2") (pintype "passive"))
      (node (ref "U1") (pin "40") (pintype "passive"))
    )
    (net (code "190") (name "/UART3_TXD") (class "Default")
      (node (ref "R6") (pin "2") (pinfunction "2_2") (pintype "passive"))
      (node (ref "U1") (pin "38") (pintype "passive"))
    )
    (net (code "191") (name "/UART4_RXD") (class "Default") (node (ref "U1") (pin "123") (pintype "passive")))
    (net (code "192") (name "/UART4_TXD") (class "Default") (node (ref "U1") (pin "121") (pintype "passive")))
    (net (code "193") (name "/UART5_RXD") (class "Default") (node (ref "U1") (pin "125") (pintype "passive")))
    (net (code "194") (name "/UART5_TXD") (class "Default") (node (ref "U1") (pin "127") (pintype "passive")))
    (net (code "195") (name "/UP") (class "Default")
      (node (ref "P8") (pin "2") (pinfunction "2_2") (pintype "passive"))
      (node (ref "U5") (pin "32") (pinfunction "PD2_(INT0)_32") (pintype "bidirectional"))
    )
    (net (code "196") (name "/USB_H1_OC") (class "Default") (node (ref "U1") (pin "73") (pintype "passive")))
    (net (code "197") (name "/USB_H1_PWR_EN") (class "Default")
      (node (ref "U1") (pin "67") (pintype "passive"))
    )
    (net (code "198") (name "/USB_H1_VBUS") (class "Default")
      (node (ref "U1") (pin "75") (pintype "passive"))
    )
    (net (code "199") (name "/USB_HOST_DN") (class "Default")
      (node (ref "U1") (pin "69") (pintype "passive"))
    )
    (net (code "200") (name "/USB_HOST_DP") (class "Default")
      (node (ref "U1") (pin "71") (pintype "passive"))
    )
    (net (code "201") (name "/USB_OTG_DN") (class "Default") (node (ref "U1") (pin "66") (pintype "passive")))
    (net (code "202") (name "/USB_OTG_DP") (class "Default") (node (ref "U1") (pin "68") (pintype "passive")))
    (net (code "203") (name "/USB_OTG_ID") (class "Default") (node (ref "U1") (pin "72") (pintype "passive")))
    (net (code "204") (name "/USB_OTG_OC") (class "Default") (node (ref "U1") (pin "62") (pintype "passive")))
    (net (code "205") (name "/USB_OTG_PWR_EN") (class "Default")
      (node (ref "U1") (pin "64") (pintype "passive"))
    )
    (net (code "206") (name "/USB_OTG_VBUS") (class "Default")
      (node (ref "U1") (pin "70") (pintype "passive"))
    )
    (net (code "207") (name "/WORK_LED") (class "Default")
      (node (ref "Q3") (pin "2") (pinfunction "B_2") (pintype "passive"))
      (node (ref "R1") (pin "2") (pinfunction "2_2") (pintype "passive"))
    )
    (net (code "208") (name "/nRESET") (class "Default")
      (node (ref "C7") (pin "2") (pinfunction "2_2") (pintype "passive"))
      (node (ref "K1") (pin "3") (pintype "passive"))
      (node (ref "K1") (pin "4") (pintype "passive"))
      (node (ref "U1") (pin "39") (pintype "passive"))
    )
    (net (code "209") (name "12V") (class "Default")
      (node (ref "C15") (pin "1") (pinfunction "1_1") (pintype "passive"))
      (node (ref "C16") (pin "2") (pinfunction "2_2") (pintype "passive"))
      (node (ref "U3") (pin "7") (pinfunction "IN_7") (pintype "passive"))
    )
    (net (code "210") (name "GEN_3V3") (class "Default")
      (node (ref "D5") (pin "1") (pinfunction "A_1") (pintype "passive"))
    )
    (net (code "211") (name "GND") (class "Default")
      (node (ref "A1") (pin "2") (pinfunction "2_2") (pintype "passive"))
      (node (ref "A1") (pin "3") (pinfunction "3_3") (pintype "passive"))
      (node (ref "C1") (pin "1") (pinfunction "1_1") (pintype "passive"))
      (node (ref "C10") (pin "2") (pintype "passive"))
      (node (ref "C11") (pin "2") (pinfunction "2_2") (pintype "passive"))
      (node (ref "C12") (pin "1") (pinfunction "1_1") (pintype "passive"))
      (node (ref "C13") (pin "2") (pintype "passive"))
      (node (ref "C14") (pin "2") (pintype "passive"))
      (node (ref "C15") (pin "2") (pinfunction "2_2") (pintype "passive"))
      (node (ref "C16") (pin "1") (pinfunction "1_1") (pintype "passive"))
      (node (ref "C17") (pin "2") (pintype "passive"))
      (node (ref "C18") (pin "2") (pintype "passive"))
      (node (ref "C2") (pin "1") (pinfunction "1_1") (pintype "passive"))
      (node (ref "C22") (pin "2") (pinfunction "2_2") (pintype "passive"))
      (node (ref "C23") (pin "2") (pinfunction "2_2") (pintype "passive"))
      (node (ref "C3") (pin "2") (pinfunction "2_2") (pintype "passive"))
      (node (ref "C4") (pin "2") (pinfunction "2_2") (pintype "passive"))
      (node (ref "C5") (pin "1") (pinfunction "1_1") (pintype "passive"))
      (node (ref "C6") (pin "2") (pinfunction "2_2") (pintype "passive"))
      (node (ref "C7") (pin "1") (pinfunction "1_1") (pintype "passive"))
      (node (ref "C8") (pin "1") (pintype "passive"))
      (node (ref "C9") (pin "2") (pinfunction "2_2") (pintype "passive"))
      (node (ref "D1") (pin "2") (pinfunction "A_2") (pintype "passive"))
      (node (ref "D2") (pin "1") (pinfunction "A_1") (pintype "passive"))
      (node (ref "D6") (pin "2") (pinfunction "A_2") (pintype "passive"))
      (node (ref "D7") (pin "2") (pinfunction "A_2") (pintype "passive"))
      (node (ref "K1") (pin "1") (pintype "passive"))
      (node (ref "K1") (pin "2") (pintype "passive"))
      (node (ref "P1") (pin "5") (pinfunction "GND_5") (pintype "passive"))
      (node (ref "P2") (pin "2") (pinfunction "2_2") (pintype "passive"))
      (node (ref "P3") (pin "3") (pinfunction "3_3") (pintype "passive"))
      (node (ref "P4") (pin "15") (pinfunction "15_15") (pintype "passive"))
      (node (ref "P4") (pin "24") (pinfunction "24_24") (pintype "passive"))
      (node (ref "P4") (pin "33") (pinfunction "33_33") (pintype "passive"))
      (node (ref "P4") (pin "44") (pinfunction "44_44") (pintype "passive"))
      (node (ref "P4") (pin "50") (pinfunction "50_50") (pintype "passive"))
      (node (ref "P4") (pin "51") (pinfunction "51_51") (pintype "passive"))
      (node (ref "P4") (pin "6") (pinfunction "6_6") (pintype "passive"))
      (node (ref "P5") (pin "2") (pinfunction "2_2") (pintype "passive"))
      (node (ref "P6") (pin "1") (pinfunction "1_1") (pintype "passive"))
      (node (ref "P7") (pin "1") (pinfunction "1_1") (pintype "passive"))
      (node (ref "Q1") (pin "1") (pinfunction "E_1") (pintype "passive"))
      (node (ref "Q2") (pin "1") (pinfunction "E_1") (pintype "passive"))
      (node (ref "Q3") (pin "1") (pinfunction "E_1") (pintype "passive"))
      (node (ref "Q4") (pin "1") (pinfunction "E_1") (pintype "passive"))
      (node (ref "R14") (pin "2") (pinfunction "2_2") (pintype "passive"))
      (node (ref "R15") (pin "1") (pinfunction "1_1") (pintype "passive"))
      (node (ref "R16") (pin "1") (pinfunction "1_1") (pintype "passive"))
      (node (ref "R17") (pin "1") (pinfunction "1_1") (pintype "passive"))
      (node (ref "R21") (pin "1") (pintype "passive"))
      (node (ref "U1") (pin "1") (pintype "passive"))
      (node (ref "U1") (pin "128") (pintype "passive"))
      (node (ref "U1") (pin "149") (pintype "passive"))
      (node (ref "U1") (pin "176") (pintype "passive"))
      (node (ref "U1") (pin "201") (pintype "passive"))
      (node (ref "U1") (pin "202") (pintype "passive"))
      (node (ref "U1") (pin "3") (pintype "passive"))
      (node (ref "U1") (pin "5") (pintype "passive"))
      (node (ref "U1") (pin "51") (pintype "passive"))
      (node (ref "U1") (pin "65") (pintype "passive"))
      (node (ref "U1") (pin "7") (pintype "passive"))
      (node (ref "U1") (pin "9") (pintype "passive"))
      (node (ref "U1") (pin "93") (pintype "passive"))
      (node (ref "U2") (pin "1") (pinfunction "AGND_1") (pintype "passive"))
      (node (ref "U2") (pin "31") (pinfunction "SIM_GND_31") (pintype "passive"))
      (node (ref "U2") (pin "35") (pinfunction "GND_35") (pintype "passive"))
      (node (ref "U2") (pin "36") (pinfunction "GND_36") (pintype "passive"))
      (node (ref "U2") (pin "37") (pinfunction "GND_37") (pintype "passive"))
      (node (ref "U2") (pin "38") (pinfunction "GND_38") (pintype "passive"))
      (node (ref "U2") (pin "40") (pinfunction "GND_40") (pintype "passive"))
      (node (ref "U3") (pin "6") (pinfunction "GND_6") (pintype "passive"))
      (node (ref "U3") (pin "9") (pinfunction "GND_9") (pintype "passive"))
      (node (ref "U4") (pin "2") (pinfunction "GND_2") (pintype "passive"))
      (node (ref "U4") (pin "3") (pinfunction "GND_3") (pintype "passive"))
      (node (ref "U5") (pin "21") (pinfunction "GND_21") (pintype "power_in"))
      (node (ref "U5") (pin "3") (pinfunction "GND_3") (pintype "power_in"))
      (node (ref "U5") (pin "5") (pinfunction "GND_5") (pintype "power_in"))
    )
    (net (code "212") (name "Net-(D2-K)") (class "Default")
      (node (ref "C20") (pin "1") (pinfunction "1_1") (pintype "passive"))
      (node (ref "D2") (pin "2") (pinfunction "K_2") (pintype "passive"))
      (node (ref "L2") (pin "1") (pinfunction "1_1") (pintype "passive"))
      (node (ref "U3") (pin "8") (pinfunction "SW_8") (pintype "passive"))
    )
    (net (code "213") (name "Net-(D3-K)") (class "Default")
      (node (ref "D3") (pin "2") (pinfunction "K_2") (pintype "passive"))
      (node (ref "R15") (pin "2") (pinfunction "2_2") (pintype "passive"))
    )
    (net (code "214") (name "Net-(D4-K)") (class "Default")
      (node (ref "D4") (pin "2") (pinfunction "K_2") (pintype "passive"))
      (node (ref "R16") (pin "2") (pinfunction "2_2") (pintype "passive"))
    )
    (net (code "215") (name "Net-(D5-K)") (class "Default")
      (node (ref "D5") (pin "2") (pinfunction "K_2") (pintype "passive"))
      (node (ref "R23") (pin "2") (pinfunction "2_2") (pintype "passive"))
    )
    (net (code "216") (name "Net-(D8-A)") (class "Default")
      (node (ref "D8") (pin "1") (pinfunction "A_1") (pintype "passive"))
      (node (ref "R10") (pin "2") (pinfunction "2_2") (pintype "passive"))
    )
    (net (code "217") (name "Net-(D8-K)") (class "Default")
      (node (ref "D8") (pin "2") (pinfunction "K_2") (pintype "passive"))
      (node (ref "Q3") (pin "3") (pinfunction "C_3") (pintype "passive"))
    )
    (net (code "218") (name "Net-(D9-A)") (class "Default")
      (node (ref "D9") (pin "1") (pinfunction "A_1") (pintype "passive"))
      (node (ref "R11") (pin "2") (pinfunction "2_2") (pintype "passive"))
    )
    (net (code "219") (name "Net-(D9-K)") (class "Default")
      (node (ref "D9") (pin "2") (pinfunction "K_2") (pintype "passive"))
      (node (ref "Q4") (pin "3") (pinfunction "C_3") (pintype "passive"))
    )
    (net (code "220") (name "Net-(P4-Pad46)") (class "Default")
      (node (ref "P4") (pin "46") (pinfunction "46_46") (pintype "passive"))
      (node (ref "R18") (pin "1") (pinfunction "1_1") (pintype "passive"))
    )
    (net (code "221") (name "Net-(P8-Pad1)") (class "Default")
      (node (ref "P8") (pin "1") (pinfunction "1_1") (pintype "passive"))
      (node (ref "P9") (pin "1") (pinfunction "1_1") (pintype "passive"))
      (node (ref "R24") (pin "2") (pinfunction "2_2") (pintype "passive"))
    )
    (net (code "222") (name "Net-(Q1-B)") (class "Default")
      (node (ref "Q1") (pin "2") (pinfunction "B_2") (pintype "passive"))
      (node (ref "R8") (pin "1") (pinfunction "1_1") (pintype "passive"))
    )
    (net (code "223") (name "Net-(Q1-C)") (class "Default")
      (node (ref "Q1") (pin "3") (pinfunction "C_3") (pintype "passive"))
      (node (ref "U2") (pin "10") (pinfunction "PWRKEY_10") (pintype "passive"))
    )
    (net (code "224") (name "Net-(Q2-B)") (class "Default")
      (node (ref "Q2") (pin "2") (pinfunction "B_2") (pintype "passive"))
      (node (ref "R9") (pin "1") (pinfunction "1_1") (pintype "passive"))
    )
    (net (code "225") (name "Net-(Q2-C)") (class "Default")
      (node (ref "C9") (pin "1") (pinfunction "1_1") (pintype "passive"))
      (node (ref "Q2") (pin "3") (pinfunction "C_3") (pintype "passive"))
      (node (ref "U2") (pin "11") (pinfunction "RESET_11") (pintype "passive"))
    )
    (net (code "226") (name "Net-(R13-Pad1)") (class "Default")
      (node (ref "R13") (pin "1") (pinfunction "1_1") (pintype "passive"))
      (node (ref "R14") (pin "1") (pinfunction "1_1") (pintype "passive"))
      (node (ref "U3") (pin "4") (pinfunction "SW_4") (pintype "passive"))
    )
    (net (code "227") (name "Net-(U2-DTR)") (class "Default")
      (node (ref "R12") (pin "1") (pinfunction "1_1") (pintype "passive"))
      (node (ref "U2") (pin "20") (pinfunction "DTR_20") (pintype "passive"))
    )
    (net (code "228") (name "Net-(U2-NETLIGHT)") (class "Default")
      (node (ref "R2") (pin "1") (pinfunction "1_1") (pintype "passive"))
      (node (ref "U2") (pin "13") (pinfunction "NETLIGHT_13") (pintype "passive"))
    )
    (net (code "229") (name "Net-(U2-RF_ANT)") (class "Default")
      (node (ref "A1") (pin "1") (pinfunction "1_1") (pintype "passive"))
      (node (ref "U2") (pin "39") (pinfunction "RF_ANT_39") (pintype "passive"))
    )
    (net (code "230") (name "Net-(U2-RX)") (class "Default")
      (node (ref "R6") (pin "1") (pinfunction "1_1") (pintype "passive"))
      (node (ref "U2") (pin "22") (pinfunction "RX_22") (pintype "passive"))
    )
    (net (code "231") (name "Net-(U2-SIM_CLK)") (class "Default")
      (node (ref "R3") (pin "2") (pinfunction "2_2") (pintype "passive"))
      (node (ref "U2") (pin "30") (pinfunction "SIM_CLK_30") (pintype "passive"))
    )
    (net (code "232") (name "Net-(U2-SIM_DATA)") (class "Default")
      (node (ref "R4") (pin "2") (pinfunction "2_2") (pintype "passive"))
      (node (ref "U2") (pin "29") (pinfunction "SIM_DATA_29") (pintype "passive"))
    )
    (net (code "233") (name "Net-(U2-SIM_RST)") (class "Default")
      (node (ref "R5") (pin "2") (pinfunction "2_2") (pintype "passive"))
      (node (ref "U2") (pin "28") (pinfunction "SIM_RST_28") (pintype "passive"))
    )
    (net (code "234") (name "Net-(U2-TX)") (class "Default")
      (node (ref "R7") (pin "1") (pinfunction "1_1") (pintype "passive"))
      (node (ref "U2") (pin "21") (pinfunction "TX_21") (pintype "passive"))
    )
    (net (code "235") (name "Net-(U3-BOOT)") (class "Default")
      (node (ref "C20") (pin "2") (pinfunction "2_2") (pintype "passive"))
      (node (ref "U3") (pin "1") (pinfunction "BOOT_1") (pintype "passive"))
    )
    (net (code "236") (name "Net-(U4-FB)") (class "Default")
      (node (ref "R19") (pin "1") (pintype "passive"))
      (node (ref "R21") (pin "2") (pintype "passive"))
      (node (ref "U4") (pin "4") (pinfunction "FB_4") (pintype "passive"))
    )
    (net (code "237") (name "Net-(U4-SW)") (class "Default")
      (node (ref "L1") (pin "1") (pintype "passive"))
      (node (ref "U4") (pin "7") (pinfunction "SW_7") (pintype "passive"))
    )
    (net (code "238") (name "Net-(U5-AREF)") (class "Default")
      (node (ref "C23") (pin "1") (pinfunction "1_1") (pintype "passive"))
      (node (ref "U5") (pin "20") (pinfunction "AREF_20") (pintype "passive"))
    )
    (net (code "239") (name "Net-(U5-PD4_(XCK{slash}T0))") (class "Default")
      (node (ref "R23") (pin "1") (pinfunction "1_1") (pintype "passive"))
      (node (ref "U5") (pin "2") (pinfunction "PD4_(XCK/T0)_2") (pintype "bidirectional"))
    )
    (net (code "240") (name "VDD3.0") (class "Default")
      (node (ref "R12") (pin "2") (pinfunction "2_2") (pintype "passive"))
      (node (ref "U2") (pin "19") (pinfunction "VDD_EXT_19") (pintype "passive"))
    )
    (net (code "241") (name "VSIM") (class "Default")
      (node (ref "C1") (pin "2") (pinfunction "2_2") (pintype "passive"))
      (node (ref "P1") (pin "1") (pinfunction "VCC_1") (pintype "passive"))
      (node (ref "U2") (pin "27") (pinfunction "SIM_VDD_27") (pintype "passive"))
    )
    (net (code "242") (name "unconnected-(P1-NC-Pad4)") (class "Default")
      (node (ref "P1") (pin "4") (pinfunction "NC_4") (pintype "passive"))
    )
    (net (code "243") (name "unconnected-(P1-NC-Pad8)") (class "Default")
      (node (ref "P1") (pin "8") (pinfunction "NC_8") (pintype "passive"))
    )
    (net (code "244") (name "unconnected-(P1-VPP-Pad6)") (class "Default")
      (node (ref "P1") (pin "6") (pinfunction "VPP_6") (pintype "passive"))
    )
    (net (code "245") (name "unconnected-(P4-Pad34)") (class "Default")
      (node (ref "P4") (pin "34") (pinfunction "34_34") (pintype "passive"))
    )
    (net (code "246") (name "unconnected-(P4-Pad35)") (class "Default")
      (node (ref "P4") (pin "35") (pinfunction "35_35") (pintype "passive"))
    )
    (net (code "247") (name "unconnected-(P4-Pad36)") (class "Default")
      (node (ref "P4") (pin "36") (pinfunction "36_36") (pintype "passive"))
    )
    (net (code "248") (name "unconnected-(P4-Pad39)") (class "Default")
      (node (ref "P4") (pin "39") (pinfunction "39_39") (pintype "passive"))
    )
    (net (code "249") (name "unconnected-(P4-Pad40)") (class "Default")
      (node (ref "P4") (pin "40") (pinfunction "40_40") (pintype "passive"))
    )
    (net (code "250") (name "unconnected-(P4-Pad47)") (class "Default")
      (node (ref "P4") (pin "47") (pinfunction "47_47") (pintype "passive"))
    )
    (net (code "251") (name "unconnected-(P4-Pad48)") (class "Default")
      (node (ref "P4") (pin "48") (pinfunction "48_48") (pintype "passive"))
    )
    (net (code "252") (name "unconnected-(P4-Pad49)") (class "Default")
      (node (ref "P4") (pin "49") (pinfunction "49_49") (pintype "passive"))
    )
    (net (code "253") (name "unconnected-(P10-Pad1)") (class "Default")
      (node (ref "P10") (pin "1") (pinfunction "1_1") (pintype "passive"))
    )
    (net (code "254") (name "unconnected-(P10-Pad2)") (class "Default")
      (node (ref "P10") (pin "2") (pinfunction "2_2") (pintype "passive"))
    )
    (net (code "255") (name "unconnected-(U2-ADC-Pad16)") (class "Default")
      (node (ref "U2") (pin "16") (pinfunction "ADC_16") (pintype "passive"))
    )
    (net (code "256") (name "unconnected-(U2-CTS-Pad23)") (class "Default")
      (node (ref "U2") (pin "23") (pinfunction "CTS_23") (pintype "passive"))
    )
    (net (code "257") (name "unconnected-(U2-DBG_R-Pad14)") (class "Default")
      (node (ref "U2") (pin "14") (pinfunction "DBG_R_14") (pintype "passive"))
    )
    (net (code "258") (name "unconnected-(U2-DBG_T-Pad15)") (class "Default")
      (node (ref "U2") (pin "15") (pinfunction "DBG_T_15") (pintype "passive"))
    )
    (net (code "259") (name "unconnected-(U2-DCD-Pad25)") (class "Default")
      (node (ref "U2") (pin "25") (pinfunction "DCD_25") (pintype "passive"))
    )
    (net (code "260") (name "unconnected-(U2-GPIO-Pad17)") (class "Default")
      (node (ref "U2") (pin "17") (pinfunction "GPIO_17") (pintype "passive"))
    )
    (net (code "261") (name "unconnected-(U2-GPIO-Pad18)") (class "Default")
      (node (ref "U2") (pin "18") (pinfunction "GPIO_18") (pintype "passive"))
    )
    (net (code "262") (name "unconnected-(U2-LOUDSPKN-Pad8)") (class "Default")
      (node (ref "U2") (pin "8") (pinfunction "LOUDSPKN_8") (pintype "passive"))
    )
    (net (code "263") (name "unconnected-(U2-LOUDSPKP-Pad9)") (class "Default")
      (node (ref "U2") (pin "9") (pinfunction "LOUDSPKP_9") (pintype "passive"))
    )
    (net (code "264") (name "unconnected-(U2-MIC1N-Pad5)") (class "Default")
      (node (ref "U2") (pin "5") (pinfunction "MIC1N_5") (pintype "passive"))
    )
    (net (code "265") (name "unconnected-(U2-MIC1P-Pad4)") (class "Default")
      (node (ref "U2") (pin "4") (pinfunction "MIC1P_4") (pintype "passive"))
    )
    (net (code "266") (name "unconnected-(U2-MIC2N-Pad3)") (class "Default")
      (node (ref "U2") (pin "3") (pinfunction "MIC2N_3") (pintype "passive"))
    )
    (net (code "267") (name "unconnected-(U2-MIC2P-Pad2)") (class "Default")
      (node (ref "U2") (pin "2") (pinfunction "MIC2P_2") (pintype "passive"))
    )
    (net (code "268") (name "unconnected-(U2-RI-Pad26)") (class "Default")
      (node (ref "U2") (pin "26") (pinfunction "RI_26") (pintype "passive"))
    )
    (net (code "269") (name "unconnected-(U2-RTS-Pad24)") (class "Default")
      (node (ref "U2") (pin "24") (pinfunction "RTS_24") (pintype "passive"))
    )
    (net (code "270") (name "unconnected-(U2-SPK1N-Pad6)") (class "Default")
      (node (ref "U2") (pin "6") (pinfunction "SPK1N_6") (pintype "passive"))
    )
    (net (code "271") (name "unconnected-(U2-SPK1P-Pad7)") (class "Default")
      (node (ref "U2") (pin "7") (pinfunction "SPK1P_7") (pintype "passive"))
    )
    (net (code "272") (name "unconnected-(U2-VRTC-Pad32)") (class "Default")
      (node (ref "U2") (pin "32") (pinfunction "VRTC_32") (pintype "passive"))
    )
    (net (code "273") (name "unconnected-(U3-EN-Pad5)") (class "Default")
      (node (ref "U3") (pin "5") (pinfunction "EN_5") (pintype "passive"))
    )
    (net (code "274") (name "unconnected-(U4-PG-Pad6)") (class "Default")
      (node (ref "U4") (pin "6") (pinfunction "PG_6") (pintype "passive"))
    )
    (net (code "275") (name "unconnected-(U5-ADC6-Pad19)") (class "Default")
      (node (ref "U5") (pin "19") (pinfunction "ADC6_19") (pintype "input"))
    )
    (net (code "276") (name "unconnected-(U5-ADC7-Pad22)") (class "Default")
      (node (ref "U5") (pin "22") (pinfunction "ADC7_22") (pintype "input"))
    )
    (net (code "277") (name "unconnected-(U5-PB1_(OC1A)-Pad13)") (class "Default")
      (node (ref "U5") (pin "13") (pinfunction "PB1_(OC1A)_13") (pintype "bidirectional"))
    )
    (net (code "278") (name "unconnected-(U5-PB2_(~{SS}{slash}OC1B)-Pad14)") (class "Default")
      (node (ref "U5") (pin "14") (pinfunction "PB2_(~{SS}/OC1B)_14") (pintype "bidirectional"))
    )
    (net (code "279") (name "unconnected-(U5-PB6_(XTAL1{slash}TOSC1)-Pad7)") (class "Default")
      (node (ref "U5") (pin "7") (pinfunction "PB6_(XTAL1/TOSC1)_7") (pintype "bidirectional"))
    )
    (net (code "280") (name "unconnected-(U5-PB7_(XTAL2{slash}TOSC2)-Pad8)") (class "Default")
      (node (ref "U5") (pin "8") (pinfunction "PB7_(XTAL2/TOSC2)_8") (pintype "bidirectional"))
    )
    (net (code "281") (name "unconnected-(U5-PC3_(ADC3)-Pad26)") (class "Default")
      (node (ref "U5") (pin "26") (pinfunction "PC3_(ADC3)_26") (pintype "bidirectional"))
    )
    (net (code "282") (name "unconnected-(U5-PC4_(ADC4{slash}SDA)-Pad27)") (class "Default")
      (node (ref "U5") (pin "27") (pinfunction "PC4_(ADC4/SDA)_27") (pintype "bidirectional"))
    )
    (net (code "283") (name "unconnected-(U5-PC5_(ADC5{slash}SCL)-Pad28)") (class "Default")
      (node (ref "U5") (pin "28") (pinfunction "PC5_(ADC5/SCL)_28") (pintype "bidirectional"))
    )
    (net (code "284") (name "unconnected-(U5-PD5_(T1)-Pad9)") (class "Default")
      (node (ref "U5") (pin "9") (pinfunction "PD5_(T1)_9") (pintype "bidirectional"))
    )
    (net (code "285") (name "unconnected-(U5-PD6_(AIN0)-Pad10)") (class "Default")
      (node (ref "U5") (pin "10") (pinfunction "PD6_(AIN0)_10") (pintype "bidirectional"))
    )
  )
)
